# 00_-Smart_Door.net
KiCad netlist of a schematic drawn in Altium Designer
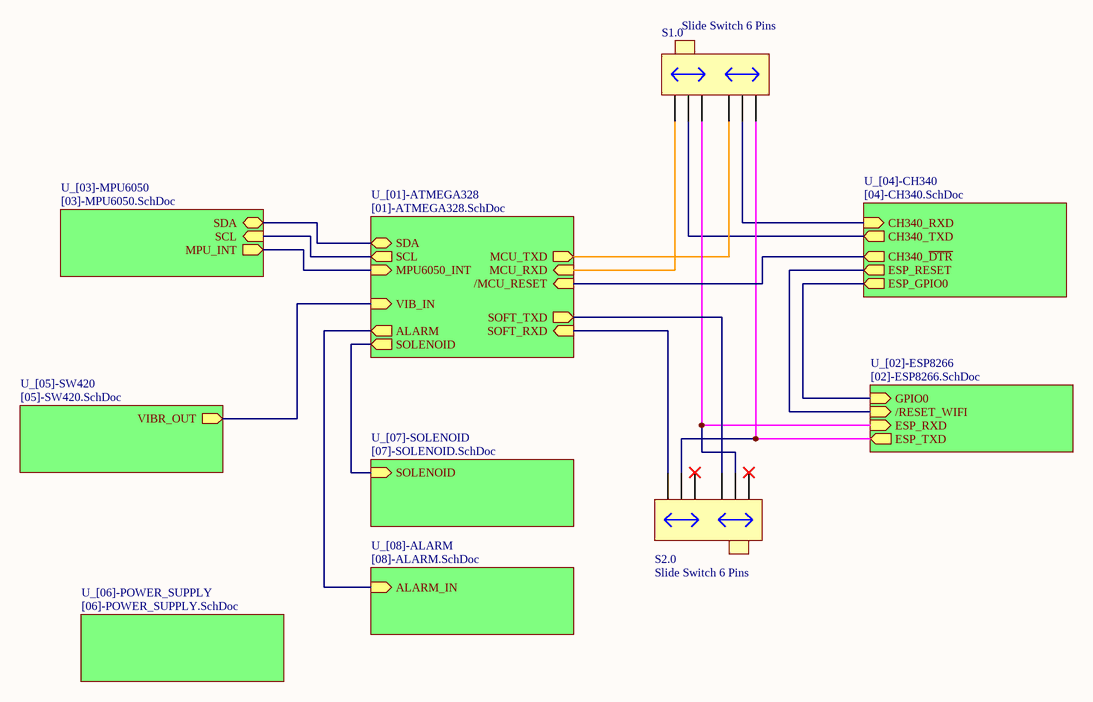
[diagram p0: [00]-Smart_Door.SchDoc]

(export (version "E")
  (design (tool "Eeschema 10.0.6"))
  (components
    (comp (ref "S1.0")
      (value "Slide Switch 6 Pins")
      (footprint "MinhTien_PCBLib:SW6_MSS-22D18")
      (description "Switch")
      (fields (field (name "PUBLISHER") "Altium Limited"))
      (libsource (lib "MinhTien_SCHLib") (part "Slide Switch 6 Pins"))
    )
    (comp (ref "S2.0")
      (value "Slide Switch 6 Pins")
      (footprint "MinhTien_PCBLib:SW6_MSS-22D18")
      (description "Switch")
      (fields (field (name "PUBLISHER") "Altium Limited"))
      (libsource (lib "") (part "Slide Switch 6 Pins_1"))
    )
  )
  (nets
    (net (code "2") (name "/CH340_RXD") (class "Default")
      (node (ref "S1.0") (pin "4") (pinfunction "COM_4") (pintype "passive"))
    )
    (net (code "3") (name "/CH340_TXD") (class "Default")
      (node (ref "S1.0") (pin "3") (pinfunction "COM_3") (pintype "passive"))
    )
    (net (code "7") (name "/ESP_RXD") (class "Default")
      (node (ref "S1.0") (pin "5") (pinfunction "NO_5") (pintype "passive"))
      (node (ref "S2.0") (pin "3") (pinfunction "COM_3") (pintype "passive"))
    )
    (net (code "8") (name "/ESP_TXD") (class "Default")
      (node (ref "S1.0") (pin "6") (pinfunction "NO_6") (pintype "passive"))
      (node (ref "S2.0") (pin "4") (pinfunction "COM_4") (pintype "passive"))
    )
    (net (code "9") (name "/MCU_RXD") (class "Default")
      (node (ref "S1.0") (pin "1") (pinfunction "NC_1") (pintype "passive"))
    )
    (net (code "10") (name "/MCU_TXD") (class "Default")
      (node (ref "S1.0") (pin "2") (pinfunction "NC_2") (pintype "passive"))
    )
    (net (code "14") (name "/SOFT_RXD") (class "Default")
      (node (ref "S2.0") (pin "6") (pinfunction "NO_6") (pintype "passive"))
    )
    (net (code "15") (name "/SOFT_TXD") (class "Default")
      (node (ref "S2.0") (pin "5") (pinfunction "NO_5") (pintype "passive"))
    )
    (net (code "18") (name "unconnected-(S2.0-NC-Pad1)") (class "Default")
      (node (ref "S2.0") (pin "1") (pinfunction "NC_1") (pintype "passive+no_connect"))
    )
    (net (code "19") (name "unconnected-(S2.0-NC-Pad2)") (class "Default")
      (node (ref "S2.0") (pin "2") (pinfunction "NC_2") (pintype "passive+no_connect"))
    )
  )
)
